# ai.net
KiCad netlist of a schematic drawn in Altium Designer
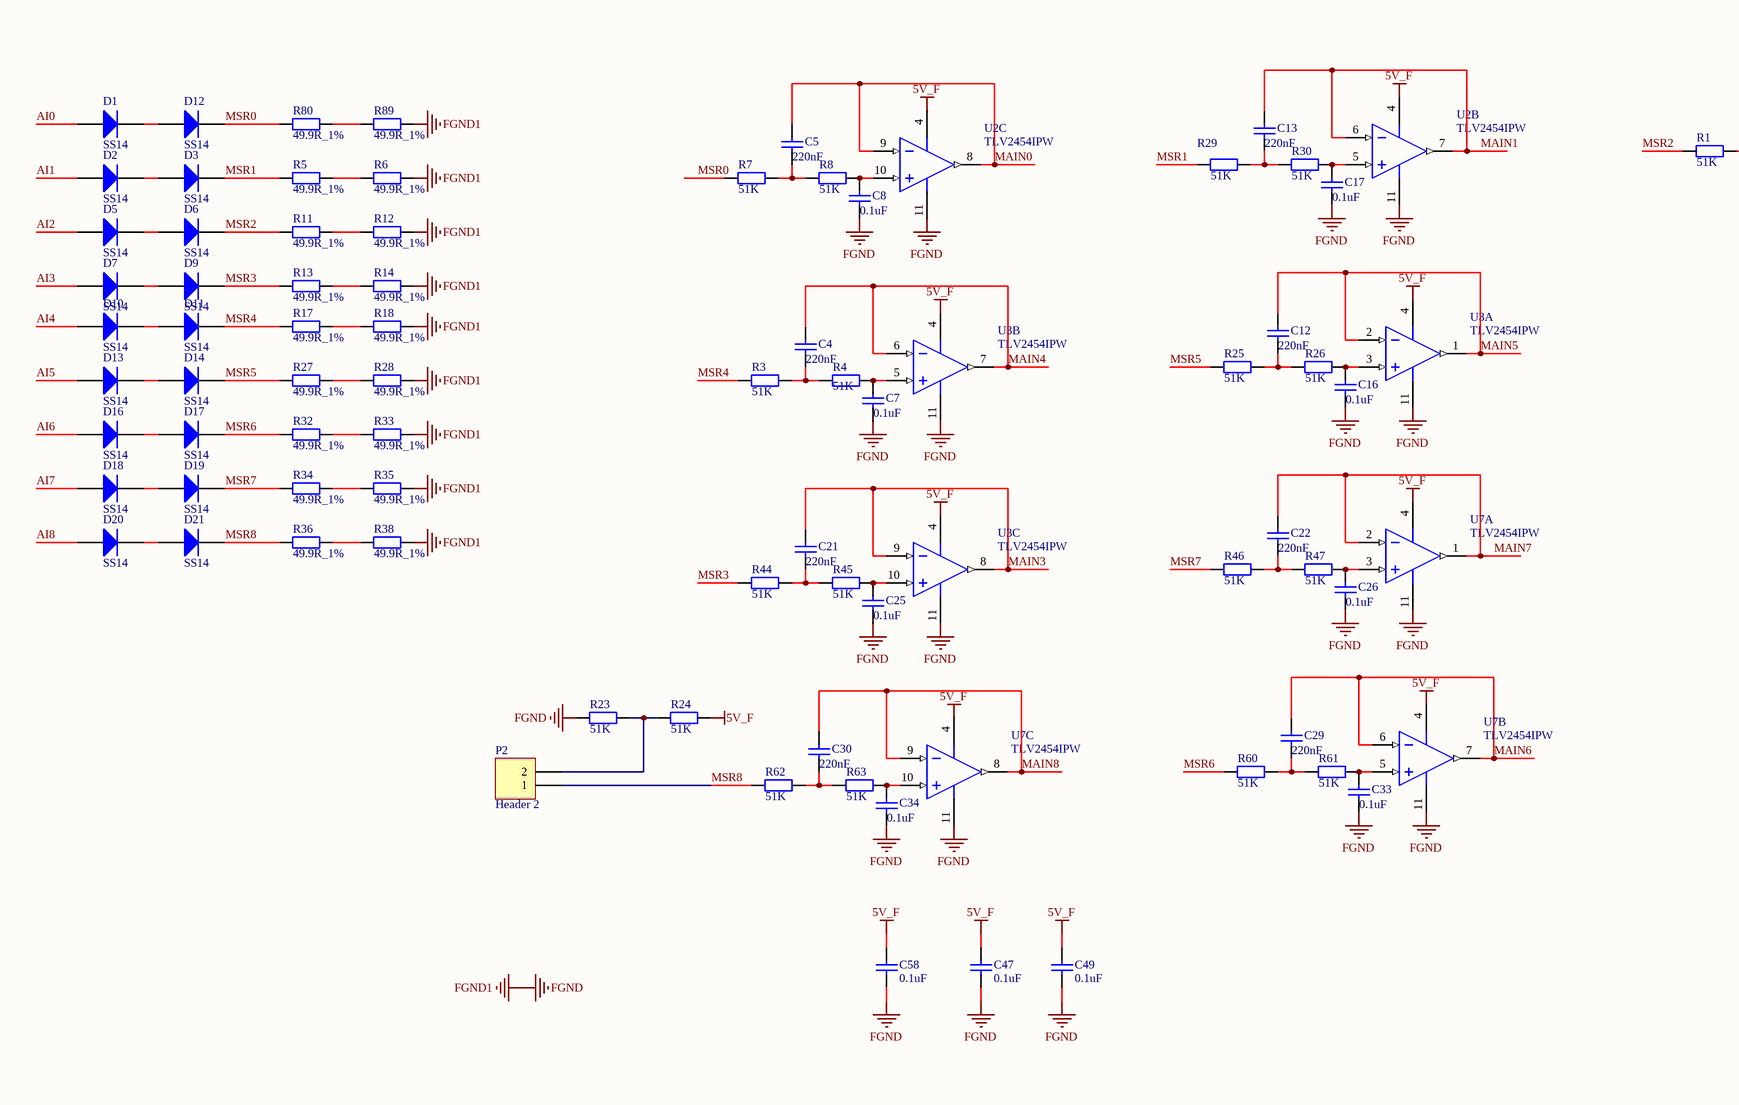
[diagram p0: ai.SchDoc, top left]
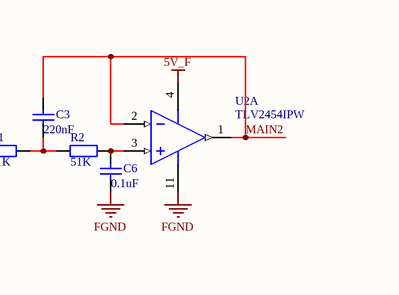
[diagram p1: ai.SchDoc, top right]
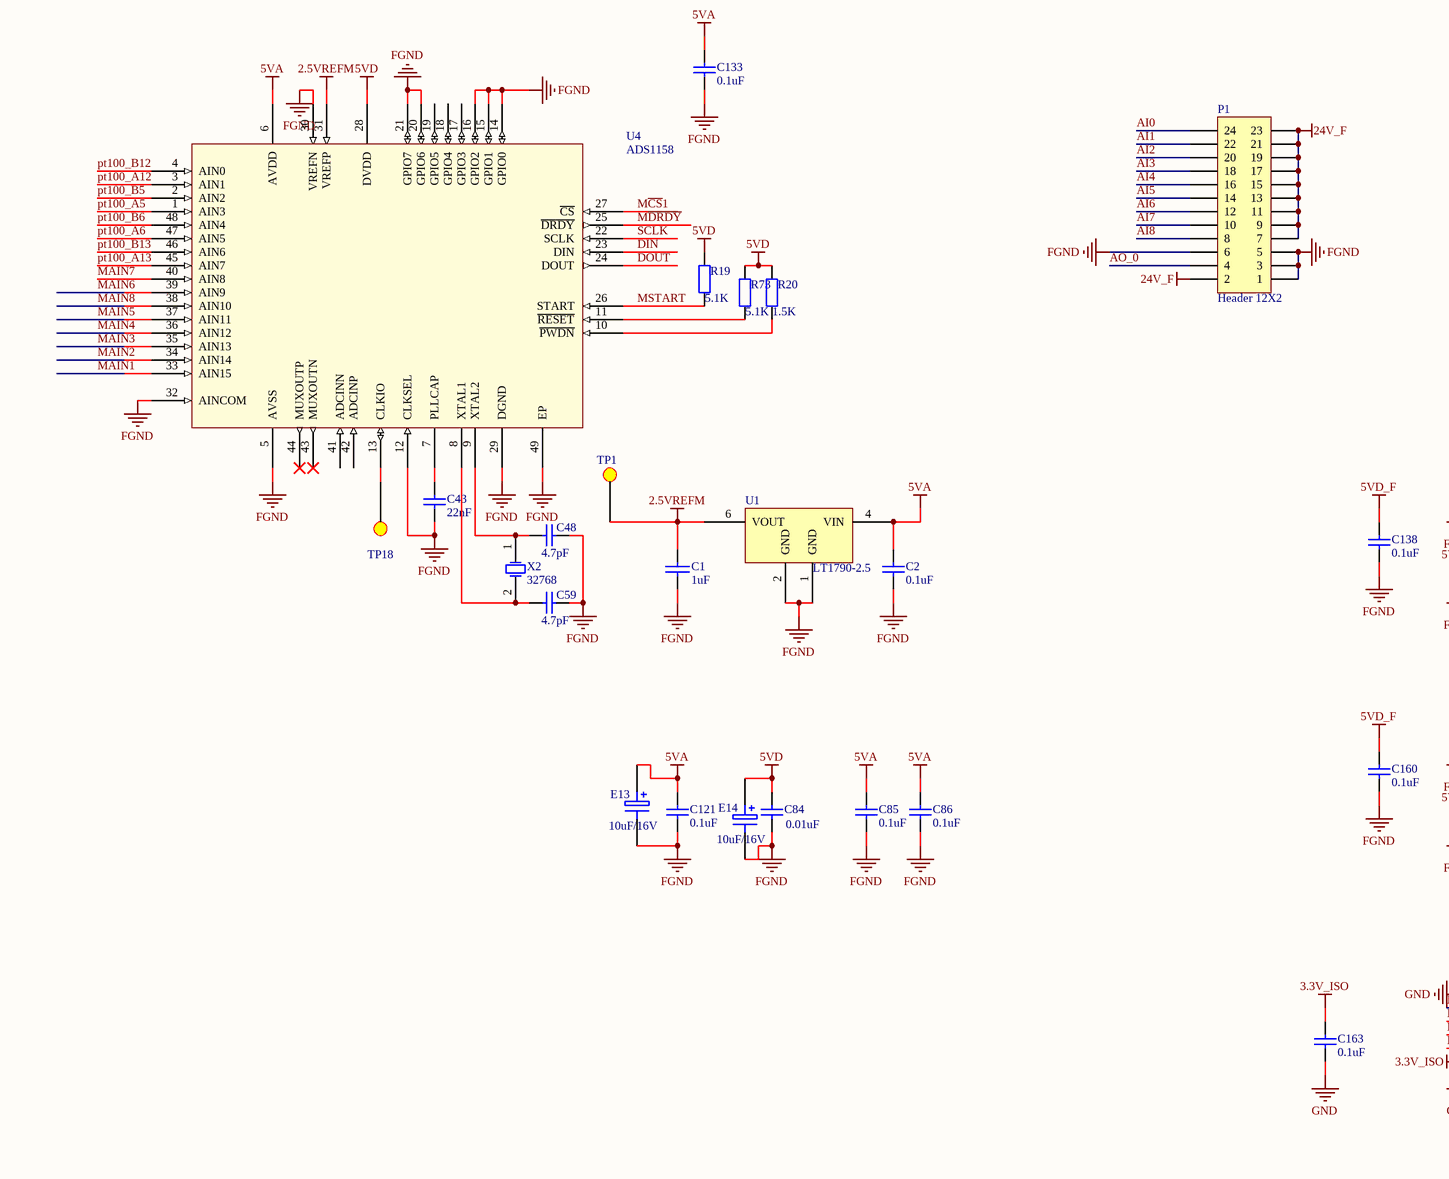
[diagram p2: ai.SchDoc, bottom left]
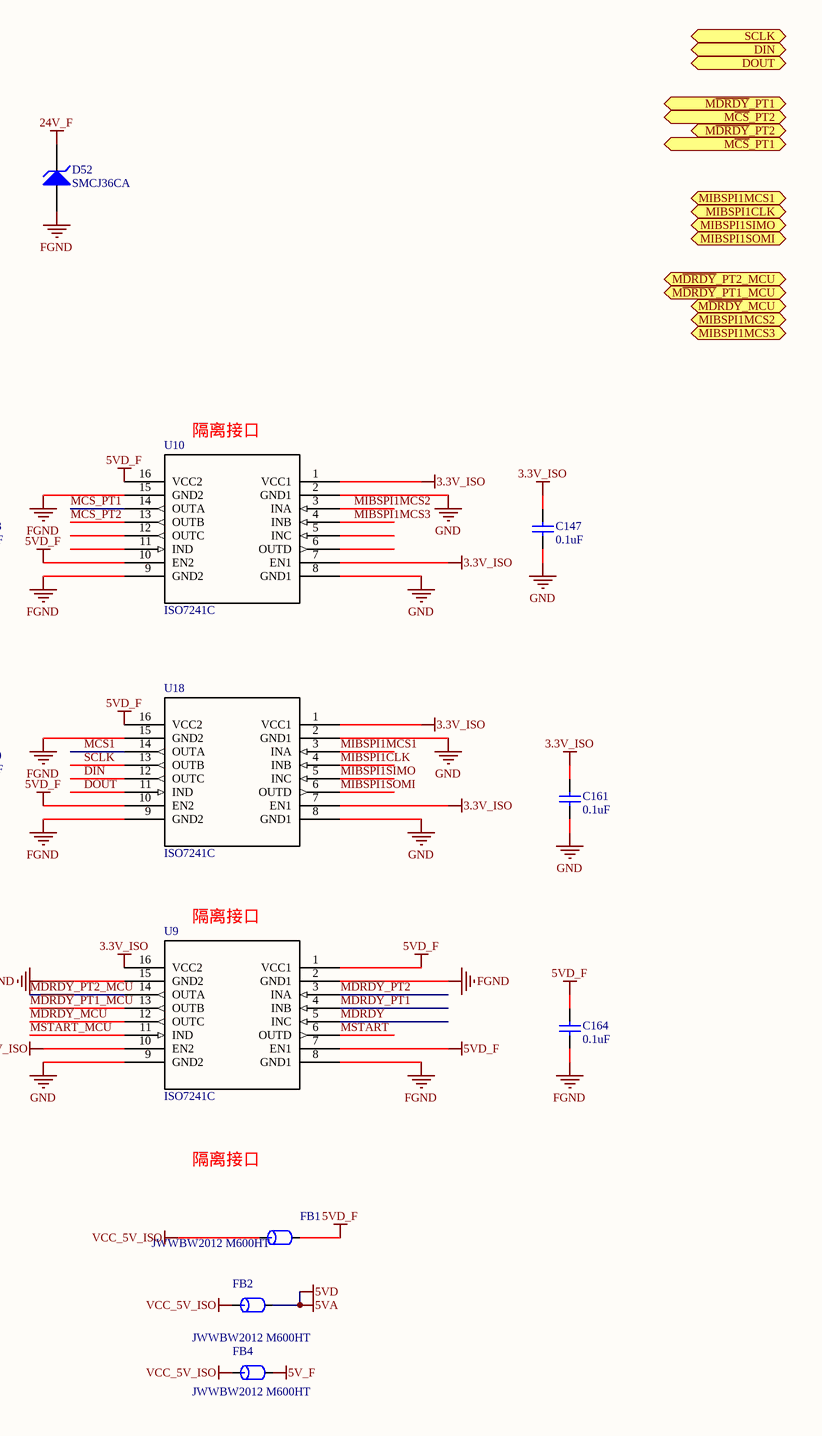
[diagram p3: ai.SchDoc, bottom right]

(export (version "E")
  (design (tool "Eeschema 10.0.6"))
  (components
    (comp (ref "C1")
      (value "1uF")
      (footprint "0603C")
      (description "Capacitor")
      (libsource (lib "*") (part "CAP"))
    )
    (comp (ref "C2")
      (value "0.1uF")
      (footprint "0603C")
      (description "Capacitor")
      (libsource (lib "Miscellaneous Devices") (part "Cap"))
    )
    (comp (ref "C3")
      (value "220nF")
      (footprint "0805C")
      (description "Capacitor")
      (libsource (lib "Miscellaneous Devices") (part "Cap"))
    )
    (comp (ref "C4")
      (value "220nF")
      (footprint "0805C")
      (description "Capacitor")
      (libsource (lib "Miscellaneous Devices") (part "Cap"))
    )
    (comp (ref "C5")
      (value "220nF")
      (footprint "0805C")
      (description "Capacitor")
      (libsource (lib "Miscellaneous Devices") (part "Cap"))
    )
    (comp (ref "C6")
      (value "0.1uF")
      (footprint "0603C")
      (description "Capacitor")
      (libsource (lib "Miscellaneous Devices") (part "Cap"))
    )
    (comp (ref "C7")
      (value "0.1uF")
      (footprint "0603C")
      (description "Capacitor")
      (libsource (lib "Miscellaneous Devices") (part "Cap"))
    )
    (comp (ref "C8")
      (value "0.1uF")
      (footprint "0603C")
      (description "Capacitor")
      (libsource (lib "Miscellaneous Devices") (part "Cap"))
    )
    (comp (ref "C12")
      (value "220nF")
      (footprint "0805C")
      (description "Capacitor")
      (libsource (lib "Miscellaneous Devices") (part "Cap"))
    )
    (comp (ref "C13")
      (value "220nF")
      (footprint "0805C")
      (description "Capacitor")
      (libsource (lib "Miscellaneous Devices") (part "Cap"))
    )
    (comp (ref "C16")
      (value "0.1uF")
      (footprint "0603C")
      (description "Capacitor")
      (libsource (lib "Miscellaneous Devices") (part "Cap"))
    )
    (comp (ref "C17")
      (value "0.1uF")
      (footprint "0603C")
      (description "Capacitor")
      (libsource (lib "Miscellaneous Devices") (part "Cap"))
    )
    (comp (ref "C21")
      (value "220nF")
      (footprint "0805C")
      (description "Capacitor")
      (libsource (lib "Miscellaneous Devices") (part "Cap"))
    )
    (comp (ref "C22")
      (value "220nF")
      (footprint "0805C")
      (description "Capacitor")
      (libsource (lib "Miscellaneous Devices") (part "Cap"))
    )
    (comp (ref "C25")
      (value "0.1uF")
      (footprint "0603C")
      (description "Capacitor")
      (libsource (lib "Miscellaneous Devices") (part "Cap"))
    )
    (comp (ref "C26")
      (value "0.1uF")
      (footprint "0603C")
      (description "Capacitor")
      (libsource (lib "Miscellaneous Devices") (part "Cap"))
    )
    (comp (ref "C29")
      (value "220nF")
      (footprint "0805C")
      (description "Capacitor")
      (libsource (lib "Miscellaneous Devices") (part "Cap"))
    )
    (comp (ref "C30")
      (value "220nF")
      (footprint "0805C")
      (description "Capacitor")
      (libsource (lib "Miscellaneous Devices") (part "Cap"))
    )
    (comp (ref "C33")
      (value "0.1uF")
      (footprint "0603C")
      (description "Capacitor")
      (libsource (lib "Miscellaneous Devices") (part "Cap"))
    )
    (comp (ref "C34")
      (value "0.1uF")
      (footprint "0603C")
      (description "Capacitor")
      (libsource (lib "Miscellaneous Devices") (part "Cap"))
    )
    (comp (ref "C43")
      (value "22nF")
      (footprint "0805C")
      (description "Capacitor")
      (libsource (lib "Miscellaneous Devices") (part "Cap"))
    )
    (comp (ref "C47")
      (value "0.1uF")
      (footprint "0603C")
      (description "Capacitor")
      (libsource (lib "Miscellaneous Devices") (part "Cap"))
    )
    (comp (ref "C48")
      (value "4.7pF")
      (footprint "0603C")
      (description "Capacitor")
      (libsource (lib "Miscellaneous Devices") (part "Cap"))
    )
    (comp (ref "C49")
      (value "0.1uF")
      (footprint "0603C")
      (description "Capacitor")
      (libsource (lib "Miscellaneous Devices") (part "Cap"))
    )
    (comp (ref "C58")
      (value "0.1uF")
      (footprint "0603C")
      (description "Capacitor")
      (libsource (lib "Miscellaneous Devices") (part "Cap"))
    )
    (comp (ref "C59")
      (value "4.7pF")
      (footprint "0603C")
      (description "Capacitor")
      (libsource (lib "Miscellaneous Devices") (part "Cap"))
    )
    (comp (ref "C84")
      (value "0.01uF")
      (footprint "0603C")
      (description "Capacitor")
      (libsource (lib "Miscellaneous Devices") (part "Cap"))
    )
    (comp (ref "C85")
      (value "0.1uF")
      (footprint "0603C")
      (description "Capacitor")
      (libsource (lib "Miscellaneous Devices") (part "Cap"))
    )
    (comp (ref "C86")
      (value "0.1uF")
      (footprint "0603C")
      (description "Capacitor")
      (libsource (lib "Miscellaneous Devices") (part "Cap"))
    )
    (comp (ref "C121")
      (value "0.1uF")
      (footprint "0603C")
      (description "Capacitor")
      (libsource (lib "Miscellaneous Devices") (part "Cap"))
    )
    (comp (ref "C133")
      (value "0.1uF")
      (footprint "0603C")
      (description "Capacitor")
      (libsource (lib "Miscellaneous Devices") (part "Cap"))
    )
    (comp (ref "C138")
      (value "0.1uF")
      (footprint "0603C")
      (description "Capacitor")
      (libsource (lib "Miscellaneous Devices") (part "Cap"))
    )
    (comp (ref "C147")
      (value "0.1uF")
      (footprint "0603C")
      (description "Capacitor")
      (libsource (lib "Miscellaneous Devices") (part "Cap"))
    )
    (comp (ref "C160")
      (value "0.1uF")
      (footprint "0603C")
      (description "Capacitor")
      (libsource (lib "Miscellaneous Devices") (part "Cap"))
    )
    (comp (ref "C161")
      (value "0.1uF")
      (footprint "0603C")
      (description "Capacitor")
      (libsource (lib "Miscellaneous Devices") (part "Cap"))
    )
    (comp (ref "C163")
      (value "0.1uF")
      (footprint "0603C")
      (description "Capacitor")
      (libsource (lib "Miscellaneous Devices") (part "Cap"))
    )
    (comp (ref "C164")
      (value "0.1uF")
      (footprint "0603C")
      (description "Capacitor")
      (libsource (lib "Miscellaneous Devices") (part "Cap"))
    )
    (comp (ref "D1")
      (value "SS14")
      (footprint "DO-214AC")
      (description "Default Diode")
      (libsource (lib "Miscellaneous Devices") (part "Diode"))
    )
    (comp (ref "D2")
      (value "SS14")
      (footprint "DO-214AC")
      (description "Default Diode")
      (libsource (lib "Miscellaneous Devices") (part "Diode"))
    )
    (comp (ref "D3")
      (value "SS14")
      (footprint "DO-214AC")
      (description "Default Diode")
      (libsource (lib "Miscellaneous Devices") (part "Diode"))
    )
    (comp (ref "D5")
      (value "SS14")
      (footprint "DO-214AC")
      (description "Default Diode")
      (libsource (lib "Miscellaneous Devices") (part "Diode"))
    )
    (comp (ref "D6")
      (value "SS14")
      (footprint "DO-214AC")
      (description "Default Diode")
      (libsource (lib "Miscellaneous Devices") (part "Diode"))
    )
    (comp (ref "D7")
      (value "SS14")
      (footprint "DO-214AC")
      (description "Default Diode")
      (libsource (lib "Miscellaneous Devices") (part "Diode"))
    )
    (comp (ref "D9")
      (value "SS14")
      (footprint "DO-214AC")
      (description "Default Diode")
      (libsource (lib "Miscellaneous Devices") (part "Diode"))
    )
    (comp (ref "D10")
      (value "SS14")
      (footprint "DO-214AC")
      (description "Default Diode")
      (libsource (lib "Miscellaneous Devices") (part "Diode"))
    )
    (comp (ref "D11")
      (value "SS14")
      (footprint "DO-214AC")
      (description "Default Diode")
      (libsource (lib "Miscellaneous Devices") (part "Diode"))
    )
    (comp (ref "D12")
      (value "SS14")
      (footprint "DO-214AC")
      (description "Default Diode")
      (libsource (lib "Miscellaneous Devices") (part "Diode"))
    )
    (comp (ref "D13")
      (value "SS14")
      (footprint "DO-214AC")
      (description "Default Diode")
      (libsource (lib "Miscellaneous Devices") (part "Diode"))
    )
    (comp (ref "D14")
      (value "SS14")
      (footprint "DO-214AC")
      (description "Default Diode")
      (libsource (lib "Miscellaneous Devices") (part "Diode"))
    )
    (comp (ref "D16")
      (value "SS14")
      (footprint "DO-214AC")
      (description "Default Diode")
      (libsource (lib "Miscellaneous Devices") (part "Diode"))
    )
    (comp (ref "D17")
      (value "SS14")
      (footprint "DO-214AC")
      (description "Default Diode")
      (libsource (lib "Miscellaneous Devices") (part "Diode"))
    )
    (comp (ref "D18")
      (value "SS14")
      (footprint "DO-214AC")
      (description "Default Diode")
      (libsource (lib "Miscellaneous Devices") (part "Diode"))
    )
    (comp (ref "D19")
      (value "SS14")
      (footprint "DO-214AC")
      (description "Default Diode")
      (libsource (lib "Miscellaneous Devices") (part "Diode"))
    )
    (comp (ref "D20")
      (value "SS14")
      (footprint "DO-214AC")
      (description "Default Diode")
      (libsource (lib "Miscellaneous Devices") (part "Diode"))
    )
    (comp (ref "D21")
      (value "SS14")
      (footprint "DO-214AC")
      (description "Default Diode")
      (libsource (lib "Miscellaneous Devices") (part "Diode"))
    )
    (comp (ref "D52")
      (value "SMCJ36CA")
      (footprint "SMC")
      (description "SMBJ36CA")
      (libsource (lib "Miscellaneous Devices") (part "D Zener"))
    )
    (comp (ref "E13")
      (value "10uF/16V")
      (footprint "C3528")
      (description "Electrolytic Capacitor")
      (libsource (lib "*") (part "ELECTRO1"))
    )
    (comp (ref "E14")
      (value "10uF/16V")
      (footprint "C3528")
      (description "Electrolytic Capacitor")
      (libsource (lib "*") (part "ELECTRO1"))
    )
    (comp (ref "FB1")
      (value "JWWBW2012 M600HT")
      (footprint "0805R")
      (libsource (lib "Schlib_20110825") (part "FB"))
    )
    (comp (ref "FB2")
      (value "JWWBW2012 M600HT")
      (footprint "0805R")
      (libsource (lib "Schlib_20110825") (part "FB"))
    )
    (comp (ref "FB4")
      (value "JWWBW2012 M600HT")
      (footprint "0805R")
      (libsource (lib "Schlib_20110825") (part "FB"))
    )
    (comp (ref "P1")
      (value "Header 12X2")
      (footprint "XH2.54_2x12")
      (description "Header, 12-Pin, Dual row")
      (libsource (lib "Miscellaneous Connectors") (part "Header 12X2"))
    )
    (comp (ref "P2")
      (value "Header 2")
      (footprint "HDR1X2")
      (description "Header, 2-Pin")
      (libsource (lib "Miscellaneous Connectors") (part "Header 2"))
    )
    (comp (ref "R1") (value "51K") (footprint "0603R") (libsource (lib "MQlibrary") (part "Res0805M")))
    (comp (ref "R2") (value "51K") (footprint "0603R") (libsource (lib "MQlibrary") (part "Res0805M")))
    (comp (ref "R3") (value "51K") (footprint "0603R") (libsource (lib "MQlibrary") (part "Res0805M")))
    (comp (ref "R4") (value "51K") (footprint "0603R") (libsource (lib "MQlibrary") (part "Res0805M")))
    (comp (ref "R5") (value "49.9R_1%") (footprint "0805R") (libsource (lib "MQlibrary") (part "Res0805M")))
    (comp (ref "R6") (value "49.9R_1%") (footprint "0805R") (libsource (lib "MQlibrary") (part "Res0805M")))
    (comp (ref "R7") (value "51K") (footprint "0603R") (libsource (lib "MQlibrary") (part "Res0805M")))
    (comp (ref "R8") (value "51K") (footprint "0603R") (libsource (lib "MQlibrary") (part "Res0805M")))
    (comp (ref "R11") (value "49.9R_1%") (footprint "0805R") (libsource (lib "MQlibrary") (part "Res0805M")))
    (comp (ref "R12") (value "49.9R_1%") (footprint "0805R") (libsource (lib "MQlibrary") (part "Res0805M")))
    (comp (ref "R13") (value "49.9R_1%") (footprint "0805R") (libsource (lib "MQlibrary") (part "Res0805M")))
    (comp (ref "R14") (value "49.9R_1%") (footprint "0805R") (libsource (lib "MQlibrary") (part "Res0805M")))
    (comp (ref "R17") (value "49.9R_1%") (footprint "0805R") (libsource (lib "MQlibrary") (part "Res0805M")))
    (comp (ref "R18") (value "49.9R_1%") (footprint "0805R") (libsource (lib "MQlibrary") (part "Res0805M")))
    (comp (ref "R19") (value "5.1K") (footprint "0603R") (libsource (lib "") (part "Res0805M_2")))
    (comp (ref "R20") (value "1.5K") (footprint "0603R") (libsource (lib "") (part "Res0805M_2")))
    (comp (ref "R23") (value "51K") (footprint "0603R") (libsource (lib "") (part "Res0805M_1")))
    (comp (ref "R24") (value "51K") (footprint "0603R") (libsource (lib "") (part "Res0805M_1")))
    (comp (ref "R25") (value "51K") (footprint "0603R") (libsource (lib "MQlibrary") (part "Res0805M")))
    (comp (ref "R26") (value "51K") (footprint "0603R") (libsource (lib "MQlibrary") (part "Res0805M")))
    (comp (ref "R27") (value "49.9R_1%") (footprint "0805R") (libsource (lib "MQlibrary") (part "Res0805M")))
    (comp (ref "R28") (value "49.9R_1%") (footprint "0805R") (libsource (lib "MQlibrary") (part "Res0805M")))
    (comp (ref "R29") (value "51K") (footprint "0603R") (libsource (lib "MQlibrary") (part "Res0805M")))
    (comp (ref "R30") (value "51K") (footprint "0603R") (libsource (lib "MQlibrary") (part "Res0805M")))
    (comp (ref "R32") (value "49.9R_1%") (footprint "0805R") (libsource (lib "MQlibrary") (part "Res0805M")))
    (comp (ref "R33") (value "49.9R_1%") (footprint "0805R") (libsource (lib "MQlibrary") (part "Res0805M")))
    (comp (ref "R34") (value "49.9R_1%") (footprint "0805R") (libsource (lib "MQlibrary") (part "Res0805M")))
    (comp (ref "R35") (value "49.9R_1%") (footprint "0805R") (libsource (lib "MQlibrary") (part "Res0805M")))
    (comp (ref "R36") (value "49.9R_1%") (footprint "0805R") (libsource (lib "MQlibrary") (part "Res0805M")))
    (comp (ref "R38") (value "49.9R_1%") (footprint "0805R") (libsource (lib "MQlibrary") (part "Res0805M")))
    (comp (ref "R44") (value "51K") (footprint "0603R") (libsource (lib "MQlibrary") (part "Res0805M")))
    (comp (ref "R45") (value "51K") (footprint "0603R") (libsource (lib "MQlibrary") (part "Res0805M")))
    (comp (ref "R46") (value "51K") (footprint "0603R") (libsource (lib "MQlibrary") (part "Res0805M")))
    (comp (ref "R47") (value "51K") (footprint "0603R") (libsource (lib "MQlibrary") (part "Res0805M")))
    (comp (ref "R60") (value "51K") (footprint "0603R") (libsource (lib "MQlibrary") (part "Res0805M")))
    (comp (ref "R61") (value "51K") (footprint "0603R") (libsource (lib "MQlibrary") (part "Res0805M")))
    (comp (ref "R62") (value "51K") (footprint "0603R") (libsource (lib "MQlibrary") (part "Res0805M")))
    (comp (ref "R63") (value "51K") (footprint "0603R") (libsource (lib "MQlibrary") (part "Res0805M")))
    (comp (ref "R73") (value "5.1K") (footprint "0603R") (libsource (lib "") (part "Res0805M_2")))
    (comp (ref "R80") (value "49.9R_1%") (footprint "0805R") (libsource (lib "MQlibrary") (part "Res0805M")))
    (comp (ref "R89") (value "49.9R_1%") (footprint "0805R") (libsource (lib "MQlibrary") (part "Res0805M")))
    (comp (ref "TP1")
      (value "TEST_POINT")
      (footprint "TPD")
      (libsource (lib "基带芯片OEM板_V1P0_张猛_20120921") (part "TEST_POINT"))
    )
    (comp (ref "TP18")
      (value "TEST_POINT")
      (footprint "TPD")
      (libsource (lib "基带芯片OEM板_V1P0_张猛_20120921") (part "TEST_POINT"))
    )
    (comp (ref "U1")
      (value "LT1790-2.5")
      (footprint "SOT23-6")
      (description "2.5V Micropower SOT-23  Low Dropout Reference")
      (libsource (lib "Schlib") (part "LT1790-2.5"))
    )
    (comp (ref "U2")
      (value "TLV2454IPW")
      (footprint "TSSOP14")
      (description "Quad High-speed, Ultra Low-power, Single-Supply TTL comparator")
      (libsource (lib "Maxim Analog Comparator") (part "MAX908EPD"))
    )
    (comp (ref "U3")
      (value "TLV2454IPW")
      (footprint "TSSOP14")
      (description "Quad High-speed, Ultra Low-power, Single-Supply TTL comparator")
      (libsource (lib "Maxim Analog Comparator") (part "MAX908EPD"))
    )
    (comp (ref "U4")
      (value "ADS1158")
      (footprint "S-PVFQN-N48")
      (description "16-Channel, 16-Bit Analog-to-Digital Converter")
      (libsource (lib "Schlib") (part "ADS1158"))
    )
    (comp (ref "U7")
      (value "TLV2454IPW")
      (footprint "TSSOP14")
      (description "Quad High-speed, Ultra Low-power, Single-Supply TTL comparator")
      (libsource (lib "Maxim Analog Comparator") (part "MAX908EPD"))
    )
    (comp (ref "U9") (value "ISO7241C") (footprint "SOIC16") (libsource (lib "DI16") (part "ISO7241C")))
    (comp (ref "U10") (value "ISO7241C") (footprint "SOIC16") (libsource (lib "DI16") (part "ISO7241C")))
    (comp (ref "U18") (value "ISO7241C") (footprint "SOIC16") (libsource (lib "DI16") (part "ISO7241C")))
    (comp (ref "X2")
      (value "32768")
      (footprint "A")
      (description "Crystal Oscillator")
      (libsource (lib "Miscellaneous Devices") (part "XTAL"))
    )
  )
  (nets
    (net (code "1") (name "/AI0") (class "Default")
      (node (ref "D1") (pin "1") (pinfunction "A_1") (pintype "passive"))
      (node (ref "P1") (pin "24") (pinfunction "24_24") (pintype "passive"))
    )
    (net (code "2") (name "/AI1") (class "Default")
      (node (ref "D2") (pin "1") (pinfunction "A_1") (pintype "passive"))
      (node (ref "P1") (pin "22") (pinfunction "22_22") (pintype "passive"))
    )
    (net (code "3") (name "/AI2") (class "Default")
      (node (ref "D5") (pin "1") (pinfunction "A_1") (pintype "passive"))
      (node (ref "P1") (pin "20") (pinfunction "20_20") (pintype "passive"))
    )
    (net (code "4") (name "/AI3") (class "Default")
      (node (ref "D7") (pin "1") (pinfunction "A_1") (pintype "passive"))
      (node (ref "P1") (pin "18") (pinfunction "18_18") (pintype "passive"))
    )
    (net (code "5") (name "/AI4") (class "Default")
      (node (ref "D10") (pin "1") (pinfunction "A_1") (pintype "passive"))
      (node (ref "P1") (pin "16") (pinfunction "16_16") (pintype "passive"))
    )
    (net (code "6") (name "/AI5") (class "Default")
      (node (ref "D13") (pin "1") (pinfunction "A_1") (pintype "passive"))
      (node (ref "P1") (pin "14") (pinfunction "14_14") (pintype "passive"))
    )
    (net (code "7") (name "/AI6") (class "Default")
      (node (ref "D16") (pin "1") (pinfunction "A_1") (pintype "passive"))
      (node (ref "P1") (pin "12") (pinfunction "12_12") (pintype "passive"))
    )
    (net (code "8") (name "/AI7") (class "Default")
      (node (ref "D18") (pin "1") (pinfunction "A_1") (pintype "passive"))
      (node (ref "P1") (pin "10") (pinfunction "10_10") (pintype "passive"))
    )
    (net (code "9") (name "/AI8") (class "Default")
      (node (ref "D20") (pin "1") (pinfunction "A_1") (pintype "passive"))
      (node (ref "P1") (pin "8") (pinfunction "8_8") (pintype "passive"))
    )
    (net (code "10") (name "/AO_0") (class "Default")
      (node (ref "P1") (pin "4") (pinfunction "4_4") (pintype "passive"))
    )
    (net (code "11") (name "/DIN") (class "Default")
      (node (ref "U18") (pin "12") (pinfunction "OUTC_12") (pintype "output"))
      (node (ref "U4") (pin "23") (pinfunction "DIN_23") (pintype "input"))
    )
    (net (code "12") (name "/DOUT") (class "Default")
      (node (ref "U18") (pin "11") (pinfunction "IND_11") (pintype "input"))
      (node (ref "U4") (pin "24") (pinfunction "DOUT_24") (pintype "output"))
    )
    (net (code "13") (name "/MAIN0") (class "Default")
      (node (ref "C5") (pin "2") (pinfunction "2_2") (pintype "passive"))
      (node (ref "U2") (pin "8") (pinfunction "OUT_8") (pintype "output"))
      (node (ref "U2") (pin "9") (pinfunction "IN-_9") (pintype "input"))
    )
    (net (code "14") (name "/MAIN1") (class "Default")
      (node (ref "C13") (pin "2") (pinfunction "2_2") (pintype "passive"))
      (node (ref "U2") (pin "6") (pinfunction "IN-_6") (pintype "input"))
      (node (ref "U2") (pin "7") (pinfunction "OUT_7") (pintype "output"))
      (node (ref "U4") (pin "33") (pinfunction "AIN15_33") (pintype "input"))
    )
    (net (code "15") (name "/MAIN2") (class "Default")
      (node (ref "C3") (pin "2") (pinfunction "2_2") (pintype "passive"))
      (node (ref "U2") (pin "1") (pinfunction "OUT_1") (pintype "output"))
      (node (ref "U2") (pin "2") (pinfunction "IN-_2") (pintype "input"))
      (node (ref "U4") (pin "34") (pinfunction "AIN14_34") (pintype "input"))
    )
    (net (code "16") (name "/MAIN3") (class "Default")
      (node (ref "C21") (pin "2") (pinfunction "2_2") (pintype "passive"))
      (node (ref "U3") (pin "8") (pinfunction "OUT_8") (pintype "output"))
      (node (ref "U3") (pin "9") (pinfunction "IN-_9") (pintype "input"))
      (node (ref "U4") (pin "35") (pinfunction "AIN13_35") (pintype "input"))
    )
    (net (code "17") (name "/MAIN4") (class "Default")
      (node (ref "C4") (pin "2") (pinfunction "2_2") (pintype "passive"))
      (node (ref "U3") (pin "6") (pinfunction "IN-_6") (pintype "input"))
      (node (ref "U3") (pin "7") (pinfunction "OUT_7") (pintype "output"))
      (node (ref "U4") (pin "36") (pinfunction "AIN12_36") (pintype "input"))
    )
    (net (code "18") (name "/MAIN5") (class "Default")
      (node (ref "C12") (pin "2") (pinfunction "2_2") (pintype "passive"))
      (node (ref "U3") (pin "1") (pinfunction "OUT_1") (pintype "output"))
      (node (ref "U3") (pin "2") (pinfunction "IN-_2") (pintype "input"))
      (node (ref "U4") (pin "37") (pinfunction "AIN11_37") (pintype "input"))
    )
    (net (code "19") (name "/MAIN6") (class "Default")
      (node (ref "C29") (pin "2") (pinfunction "2_2") (pintype "passive"))
      (node (ref "U4") (pin "39") (pinfunction "AIN9_39") (pintype "input"))
      (node (ref "U7") (pin "6") (pinfunction "IN-_6") (pintype "input"))
      (node (ref "U7") (pin "7") (pinfunction "OUT_7") (pintype "output"))
    )
    (net (code "20") (name "/MAIN7") (class "Default")
      (node (ref "C22") (pin "2") (pinfunction "2_2") (pintype "passive"))
      (node (ref "U4") (pin "40") (pinfunction "AIN8_40") (pintype "input"))
      (node (ref "U7") (pin "1") (pinfunction "OUT_1") (pintype "output"))
      (node (ref "U7") (pin "2") (pinfunction "IN-_2") (pintype "input"))
    )
    (net (code "21") (name "/MAIN8") (class "Default")
      (node (ref "C30") (pin "2") (pinfunction "2_2") (pintype "passive"))
      (node (ref "U4") (pin "38") (pinfunction "AIN10_38") (pintype "input"))
      (node (ref "U7") (pin "8") (pinfunction "OUT_8") (pintype "output"))
      (node (ref "U7") (pin "9") (pinfunction "IN-_9") (pintype "input"))
    )
    (net (code "22") (name "/MIBSPI1CLK") (class "Default")
      (node (ref "U18") (pin "4") (pinfunction "INB_4") (pintype "input"))
    )
    (net (code "23") (name "/MIBSPI1MCS1") (class "Default")
      (node (ref "U18") (pin "3") (pinfunction "INA_3") (pintype "input"))
    )
    (net (code "24") (name "/MIBSPI1MCS2") (class "Default")
      (node (ref "U10") (pin "3") (pinfunction "INA_3") (pintype "input"))
    )
    (net (code "25") (name "/MIBSPI1MCS3") (class "Default")
      (node (ref "U10") (pin "4") (pinfunction "INB_4") (pintype "input"))
    )
    (net (code "26") (name "/MIBSPI1SIMO") (class "Default")
      (node (ref "U18") (pin "5") (pinfunction "INC_5") (pintype "input"))
    )
    (net (code "27") (name "/MIBSPI1SOMI") (class "Default")
      (node (ref "U18") (pin "6") (pinfunction "OUTD_6") (pintype "output"))
    )
    (net (code "28") (name "/MSR0") (class "Default")
      (node (ref "D12") (pin "2") (pinfunction "K_2") (pintype "passive"))
      (node (ref "R7") (pin "2") (pinfunction "2_2") (pintype "passive"))
      (node (ref "R80") (pin "2") (pinfunction "2_2") (pintype "passive"))
    )
    (net (code "29") (name "/MSR1") (class "Default")
      (node (ref "D3") (pin "2") (pinfunction "K_2") (pintype "passive"))
      (node (ref "R29") (pin "2") (pinfunction "2_2") (pintype "passive"))
      (node (ref "R5") (pin "2") (pinfunction "2_2") (pintype "passive"))
    )
    (net (code "30") (name "/MSR2") (class "Default")
      (node (ref "D6") (pin "2") (pinfunction "K_2") (pintype "passive"))
      (node (ref "R1") (pin "2") (pinfunction "2_2") (pintype "passive"))
      (node (ref "R11") (pin "2") (pinfunction "2_2") (pintype "passive"))
    )
    (net (code "31") (name "/MSR3") (class "Default")
      (node (ref "D9") (pin "2") (pinfunction "K_2") (pintype "passive"))
      (node (ref "R13") (pin "2") (pinfunction "2_2") (pintype "passive"))
      (node (ref "R44") (pin "2") (pinfunction "2_2") (pintype "passive"))
    )
    (net (code "32") (name "/MSR4") (class "Default")
      (node (ref "D11") (pin "2") (pinfunction "K_2") (pintype "passive"))
      (node (ref "R17") (pin "2") (pinfunction "2_2") (pintype "passive"))
      (node (ref "R3") (pin "2") (pinfunction "2_2") (pintype "passive"))
    )
    (net (code "33") (name "/MSR5") (class "Default")
      (node (ref "D14") (pin "2") (pinfunction "K_2") (pintype "passive"))
      (node (ref "R25") (pin "2") (pinfunction "2_2") (pintype "passive"))
      (node (ref "R27") (pin "2") (pinfunction "2_2") (pintype "passive"))
    )
    (net (code "34") (name "/MSR6") (class "Default")
      (node (ref "D17") (pin "2") (pinfunction "K_2") (pintype "passive"))
      (node (ref "R32") (pin "2") (pinfunction "2_2") (pintype "passive"))
      (node (ref "R60") (pin "2") (pinfunction "2_2") (pintype "passive"))
    )
    (net (code "35") (name "/MSR7") (class "Default")
      (node (ref "D19") (pin "2") (pinfunction "K_2") (pintype "passive"))
      (node (ref "R34") (pin "2") (pinfunction "2_2") (pintype "passive"))
      (node (ref "R46") (pin "2") (pinfunction "2_2") (pintype "passive"))
    )
    (net (code "36") (name "/MSR8") (class "Default")
      (node (ref "D21") (pin "2") (pinfunction "K_2") (pintype "passive"))
      (node (ref "P2") (pin "1") (pinfunction "1_1") (pintype "passive"))
      (node (ref "R36") (pin "2") (pinfunction "2_2") (pintype "passive"))
      (node (ref "R62") (pin "2") (pinfunction "2_2") (pintype "passive"))
    )
    (net (code "37") (name "/MSTART") (class "Default")
      (node (ref "R19") (pin "2") (pinfunction "2_2") (pintype "passive"))
      (node (ref "U4") (pin "26") (pinfunction "START_26") (pintype "input"))
      (node (ref "U9") (pin "6") (pinfunction "OUTD_6") (pintype "output"))
    )
    (net (code "38") (name "/MSTART_MCU") (class "Default")
      (node (ref "U9") (pin "11") (pinfunction "IND_11") (pintype "input"))
    )
    (net (code "39") (name "/M~{CS}1") (class "Default")
      (node (ref "U18") (pin "14") (pinfunction "OUTA_14") (pintype "output"))
      (node (ref "U4") (pin "27") (pinfunction "~{CS}_27") (pintype "input"))
    )
    (net (code "40") (name "/M~{CS}_PT1") (class "Default")
      (node (ref "U10") (pin "14") (pinfunction "OUTA_14") (pintype "output"))
    )
    (net (code "41") (name "/M~{CS}_PT2") (class "Default")
      (node (ref "U10") (pin "13") (pinfunction "OUTB_13") (pintype "output"))
    )
    (net (code "42") (name "/M~{DRDY}") (class "Default")
      (node (ref "U4") (pin "25") (pinfunction "~{DRDY}_25") (pintype "output"))
      (node (ref "U9") (pin "5") (pinfunction "INC_5") (pintype "input"))
    )
    (net (code "43") (name "/M~{DRDY}_MCU") (class "Default")
      (node (ref "U9") (pin "12") (pinfunction "OUTC_12") (pintype "output"))
    )
    (net (code "44") (name "/M~{DRDY}_PT1") (class "Default")
      (node (ref "U9") (pin "4") (pinfunction "INB_4") (pintype "input"))
    )
    (net (code "45") (name "/M~{DRDY}_PT1_MCU") (class "Default")
      (node (ref "U9") (pin "13") (pinfunction "OUTB_13") (pintype "output"))
    )
    (net (code "46") (name "/M~{DRDY}_PT2") (class "Default")
      (node (ref "U9") (pin "3") (pinfunction "INA_3") (pintype "input"))
    )
    (net (code "47") (name "/M~{DRDY}_PT2_MCU") (class "Default")
      (node (ref "U9") (pin "14") (pinfunction "OUTA_14") (pintype "output"))
    )
    (net (code "48") (name "/SCLK") (class "Default")
      (node (ref "U18") (pin "13") (pinfunction "OUTB_13") (pintype "output"))
      (node (ref "U4") (pin "22") (pinfunction "SCLK_22") (pintype "input"))
    )
    (net (code "49") (name "/pt100_A5") (class "Default")
      (node (ref "U4") (pin "1") (pinfunction "AIN3_1") (pintype "input"))
    )
    (net (code "50") (name "/pt100_A6") (class "Default")
      (node (ref "U4") (pin "47") (pinfunction "AIN5_47") (pintype "input"))
    )
    (net (code "51") (name "/pt100_A12") (class "Default")
      (node (ref "U4") (pin "3") (pinfunction "AIN1_3") (pintype "input"))
    )
    (net (code "52") (name "/pt100_A13") (class "Default")
      (node (ref "U4") (pin "45") (pinfunction "AIN7_45") (pintype "input"))
    )
    (net (code "53") (name "/pt100_B5") (class "Default")
      (node (ref "U4") (pin "2") (pinfunction "AIN2_2") (pintype "input"))
    )
    (net (code "54") (name "/pt100_B6") (class "Default")
      (node (ref "U4") (pin "48") (pinfunction "AIN4_48") (pintype "input"))
    )
    (net (code "55") (name "/pt100_B12") (class "Default")
      (node (ref "U4") (pin "4") (pinfunction "AIN0_4") (pintype "input"))
    )
    (net (code "56") (name "/pt100_B13") (class "Default")
      (node (ref "U4") (pin "46") (pinfunction "AIN6_46") (pintype "input"))
    )
    (net (code "57") (name "2.5VREFM") (class "Default")
      (node (ref "C1") (pin "1") (pinfunction "1_1") (pintype "passive"))
      (node (ref "TP1") (pin "1") (pinfunction "1_1") (pintype "passive"))
      (node (ref "U1") (pin "6") (pinfunction "VOUT_6") (pintype "power_in"))
      (node (ref "U4") (pin "31") (pinfunction "VREFP_31") (pintype "input"))
    )
    (net (code "58") (name "3.3V_ISO") (class "Default")
      (node (ref "C147") (pin "2") (pinfunction "2_2") (pintype "passive"))
      (node (ref "C161") (pin "2") (pinfunction "2_2") (pintype "passive"))
      (node (ref "C163") (pin "2") (pinfunction "2_2") (pintype "passive"))
      (node (ref "U10") (pin "1") (pinfunction "VCC1_1") (pintype "power_in"))
      (node (ref "U10") (pin "7") (pinfunction "EN1_7") (pintype "passive"))
      (node (ref "U18") (pin "1") (pinfunction "VCC1_1") (pintype "power_in"))
      (node (ref "U18") (pin "7") (pinfunction "EN1_7") (pintype "passive"))
      (node (ref "U9") (pin "10") (pinfunction "EN2_10") (pintype "passive"))
      (node (ref "U9") (pin "16") (pinfunction "VCC2_16") (pintype "power_in"))
    )
    (net (code "59") (name "5VA") (class "Default")
      (node (ref "C121") (pin "2") (pinfunction "2_2") (pintype "passive"))
      (node (ref "C133") (pin "2") (pinfunction "2_2") (pintype "passive"))
      (node (ref "C2") (pin "2") (pinfunction "2_2") (pintype "passive"))
      (node (ref "C84") (pin "2") (pinfunction "2_2") (pintype "passive"))
      (node (ref "C85") (pin "2") (pinfunction "2_2") (pintype "passive"))
      (node (ref "C86") (pin "2") (pinfunction "2_2") (pintype "passive"))
      (node (ref "E13") (pin "1") (pinfunction "1_1") (pintype "passive"))
      (node (ref "E14") (pin "1") (pinfunction "1_1") (pintype "passive"))
      (node (ref "FB2") (pin "2") (pintype "passive"))
      (node (ref "R19") (pin "1") (pinfunction "1_1") (pintype "passive"))
      (node (ref "R20") (pin "1") (pinfunction "1_1") (pintype "passive"))
      (node (ref "R73") (pin "1") (pinfunction "1_1") (pintype "passive"))
      (node (ref "U1") (pin "4") (pinfunction "VIN_4") (pintype "power_in"))
      (node (ref "U4") (pin "28") (pinfunction "DVDD_28") (pintype "power_in"))
      (node (ref "U4") (pin "6") (pinfunction "AVDD_6") (pintype "passive"))
    )
    (net (code "60") (name "5VD_F") (class "Default")
      (node (ref "C138") (pin "2") (pinfunction "2_2") (pintype "passive"))
      (node (ref "C160") (pin "2") (pinfunction "2_2") (pintype "passive"))
      (node (ref "C164") (pin "2") (pinfunction "2_2") (pintype "passive"))
      (node (ref "FB1") (pin "2") (pintype "passive"))
      (node (ref "U10") (pin "10") (pinfunction "EN2_10") (pintype "passive"))
      (node (ref "U10") (pin "16") (pinfunction "VCC2_16") (pintype "power_in"))
      (node (ref "U18") (pin "10") (pinfunction "EN2_10") (pintype "passive"))
      (node (ref "U18") (pin "16") (pinfunction "VCC2_16") (pintype "power_in"))
      (node (ref "U9") (pin "1") (pinfunction "VCC1_1") (pintype "power_in"))
      (node (ref "U9") (pin "7") (pinfunction "EN1_7") (pintype "passive"))
    )
    (net (code "61") (name "5V_F") (class "Default")
      (node (ref "C47") (pin "2") (pinfunction "2_2") (pintype "passive"))
      (node (ref "C49") (pin "2") (pinfunction "2_2") (pintype "passive"))
      (node (ref "C58") (pin "2") (pinfunction "2_2") (pintype "passive"))
      (node (ref "FB4") (pin "2") (pintype "passive"))
      (node (ref "R24") (pin "2") (pinfunction "2_2") (pintype "passive"))
      (node (ref "U2") (pin "4") (pinfunction "V+_4") (pintype "power_in"))
      (node (ref "U3") (pin "4") (pinfunction "V+_4") (pintype "power_in"))
      (node (ref "U7") (pin "4") (pinfunction "V+_4") (pintype "power_in"))
    )
    (net (code "62") (name "24V_F") (class "Default")
      (node (ref "D52") (pin "2") (pinfunction "K_2") (pintype "passive"))
      (node (ref "P1") (pin "11") (pinfunction "11_11") (pintype "passive"))
      (node (ref "P1") (pin "13") (pinfunction "13_13") (pintype "passive"))
      (node (ref "P1") (pin "15") (pinfunction "15_15") (pintype "passive"))
      (node (ref "P1") (pin "17") (pinfunction "17_17") (pintype "passive"))
      (node (ref "P1") (pin "19") (pinfunction "19_19") (pintype "passive"))
      (node (ref "P1") (pin "2") (pinfunction "2_2") (pintype "passive"))
      (node (ref "P1") (pin "21") (pinfunction "21_21") (pintype "passive"))
      (node (ref "P1") (pin "23") (pinfunction "23_23") (pintype "passive"))
      (node (ref "P1") (pin "7") (pinfunction "7_7") (pintype "passive"))
      (node (ref "P1") (pin "9") (pinfunction "9_9") (pintype "passive"))
    )
    (net (code "63") (name "FGND") (class "Default")
      (node (ref "C1") (pin "2") (pinfunction "2_2") (pintype "passive"))
      (node (ref "C121") (pin "1") (pinfunction "1_1") (pintype "passive"))
      (node (ref "C133") (pin "1") (pinfunction "1_1") (pintype "passive"))
      (node (ref "C138") (pin "1") (pinfunction "1_1") (pintype "passive"))
      (node (ref "C16") (pin "1") (pinfunction "1_1") (pintype "passive"))
      (node (ref "C160") (pin "1") (pinfunction "1_1") (pintype "passive"))
      (node (ref "C164") (pin "1") (pinfunction "1_1") (pintype "passive"))
      (node (ref "C17") (pin "1") (pinfunction "1_1") (pintype "passive"))
      (node (ref "C2") (pin "1") (pinfunction "1_1") (pintype "passive"))
      (node (ref "C25") (pin "1") (pinfunction "1_1") (pintype "passive"))
      (node (ref "C26") (pin "1") (pinfunction "1_1") (pintype "passive"))
      (node (ref "C33") (pin "1") (pinfunction "1_1") (pintype "passive"))
      (node (ref "C34") (pin "1") (pinfunction "1_1") (pintype "passive"))
      (node (ref "C43") (pin "2") (pinfunction "2_2") (pintype "passive"))
      (node (ref "C47") (pin "1") (pinfunction "1_1") (pintype "passive"))
      (node (ref "C48") (pin "2") (pinfunction "2_2") (pintype "passive"))
      (node (ref "C49") (pin "1") (pinfunction "1_1") (pintype "passive"))
      (node (ref "C58") (pin "1") (pinfunction "1_1") (pintype "passive"))
      (node (ref "C59") (pin "2") (pinfunction "2_2") (pintype "passive"))
      (node (ref "C6") (pin "1") (pinfunction "1_1") (pintype "passive"))
      (node (ref "C7") (pin "1") (pinfunction "1_1") (pintype "passive"))
      (node (ref "C8") (pin "1") (pinfunction "1_1") (pintype "passive"))
      (node (ref "C84") (pin "1") (pinfunction "1_1") (pintype "passive"))
      (node (ref "C85") (pin "1") (pinfunction "1_1") (pintype "passive"))
      (node (ref "C86") (pin "1") (pinfunction "1_1") (pintype "passive"))
      (node (ref "D52") (pin "1") (pinfunction "A_1") (pintype "passive"))
      (node (ref "E13") (pin "2") (pinfunction "2_2") (pintype "passive"))
      (node (ref "E14") (pin "2") (pinfunction "2_2") (pintype "passive"))
      (node (ref "P1") (pin "1") (pinfunction "1_1") (pintype "passive"))
      (node (ref "P1") (pin "3") (pinfunction "3_3") (pintype "passive"))
      (node (ref "P1") (pin "5") (pinfunction "5_5") (pintype "passive"))
      (node (ref "P1") (pin "6") (pinfunction "6_6") (pintype "passive"))
      (node (ref "R12") (pin "1") (pinfunction "1_1") (pintype "passive"))
      (node (ref "R14") (pin "1") (pinfunction "1_1") (pintype "passive"))
      (node (ref "R18") (pin "1") (pinfunction "1_1") (pintype "passive"))
      (node (ref "R23") (pin "1") (pinfunction "1_1") (pintype "passive"))
      (node (ref "R28") (pin "1") (pinfunction "1_1") (pintype "passive"))
      (node (ref "R33") (pin "1") (pinfunction "1_1") (pintype "passive"))
      (node (ref "R35") (pin "1") (pinfunction "1_1") (pintype "passive"))
      (node (ref "R38") (pin "1") (pinfunction "1_1") (pintype "passive"))
      (node (ref "R6") (pin "1") (pinfunction "1_1") (pintype "passive"))
      (node (ref "R89") (pin "1") (pinfunction "1_1") (pintype "passive"))
      (node (ref "U1") (pin "1") (pinfunction "GND_1") (pintype "power_in"))
      (node (ref "U1") (pin "2") (pinfunction "GND_2") (pintype "power_in"))
      (node (ref "U10") (pin "15") (pinfunction "GND2_15") (pintype "power_in"))
      (node (ref "U10") (pin "9") (pinfunction "GND2_9") (pintype "power_in"))
      (node (ref "U18") (pin "15") (pinfunction "GND2_15") (pintype "power_in"))
      (node (ref "U18") (pin "9") (pinfunction "GND2_9") (pintype "power_in"))
      (node (ref "U2") (pin "11") (pinfunction "GND_11") (pintype "power_in"))
      (node (ref "U3") (pin "11") (pinfunction "GND_11") (pintype "power_in"))
      (node (ref "U4") (pin "12") (pinfunction "CLKSEL_12") (pintype "input"))
      (node (ref "U4") (pin "14") (pinfunction "GPIO0_14") (pintype "bidirectional"))
      (node (ref "U4") (pin "15") (pinfunction "GPIO1_15") (pintype "bidirectional"))
      (node (ref "U4") (pin "16") (pinfunction "GPIO2_16") (pintype "bidirectional"))
      (node (ref "U4") (pin "20") (pinfunction "GPIO6_20") (pintype "bidirectional"))
      (node (ref "U4") (pin "21") (pinfunction "GPIO7_21") (pintype "bidirectional"))
      (node (ref "U4") (pin "29") (pinfunction "DGND_29") (pintype "power_in"))
      (node (ref "U4") (pin "30") (pinfunction "VREFN_30") (pintype "input"))
      (node (ref "U4") (pin "32") (pinfunction "AINCOM_32") (pintype "input"))
      (node (ref "U4") (pin "49") (pinfunction "EP_49") (pintype "passive"))
      (node (ref "U4") (pin "5") (pinfunction "AVSS_5") (pintype "power_in"))
      (node (ref "U7") (pin "11") (pinfunction "GND_11") (pintype "power_in"))
      (node (ref "U9") (pin "2") (pinfunction "GND1_2") (pintype "power_in"))
      (node (ref "U9") (pin "8") (pinfunction "GND1_8") (pintype "power_in"))
    )
    (net (code "64") (name "GND") (class "Default")
      (node (ref "C147") (pin "1") (pinfunction "1_1") (pintype "passive"))
      (node (ref "C161") (pin "1") (pinfunction "1_1") (pintype "passive"))
      (node (ref "C163") (pin "1") (pinfunction "1_1") (pintype "passive"))
      (node (ref "U10") (pin "2") (pinfunction "GND1_2") (pintype "power_in"))
      (node (ref "U10") (pin "8") (pinfunction "GND1_8") (pintype "power_in"))
      (node (ref "U18") (pin "2") (pinfunction "GND1_2") (pintype "power_in"))
      (node (ref "U18") (pin "8") (pinfunction "GND1_8") (pintype "power_in"))
      (node (ref "U9") (pin "15") (pinfunction "GND2_15") (pintype "power_in"))
      (node (ref "U9") (pin "9") (pinfunction "GND2_9") (pintype "power_in"))
    )
    (net (code "65") (name "Net-(C3-Pad1)") (class "Default")
      (node (ref "C3") (pin "1") (pinfunction "1_1") (pintype "passive"))
      (node (ref "R1") (pin "1") (pinfunction "1_1") (pintype "passive"))
      (node (ref "R2") (pin "2") (pinfunction "2_2") (pintype "passive"))
    )
    (net (code "66") (name "Net-(C4-Pad1)") (class "Default")
      (node (ref "C4") (pin "1") (pinfunction "1_1") (pintype "passive"))
      (node (ref "R3") (pin "1") (pinfunction "1_1") (pintype "passive"))
      (node (ref "R4") (pin "2") (pinfunction "2_2") (pintype "passive"))
    )
    (net (code "67") (name "Net-(C5-Pad1)") (class "Default")
      (node (ref "C5") (pin "1") (pinfunction "1_1") (pintype "passive"))
      (node (ref "R7") (pin "1") (pinfunction "1_1") (pintype "passive"))
      (node (ref "R8") (pin "2") (pinfunction "2_2") (pintype "passive"))
    )
    (net (code "68") (name "Net-(C12-Pad1)") (class "Default")
      (node (ref "C12") (pin "1") (pinfunction "1_1") (pintype "passive"))
      (node (ref "R25") (pin "1") (pinfunction "1_1") (pintype "passive"))
      (node (ref "R26") (pin "2") (pinfunction "2_2") (pintype "passive"))
    )
    (net (code "69") (name "Net-(C13-Pad1)") (class "Default")
      (node (ref "C13") (pin "1") (pinfunction "1_1") (pintype "passive"))
      (node (ref "R29") (pin "1") (pinfunction "1_1") (pintype "passive"))
      (node (ref "R30") (pin "2") (pinfunction "2_2") (pintype "passive"))
    )
    (net (code "70") (name "Net-(C21-Pad1)") (class "Default")
      (node (ref "C21") (pin "1") (pinfunction "1_1") (pintype "passive"))
      (node (ref "R44") (pin "1") (pinfunction "1_1") (pintype "passive"))
      (node (ref "R45") (pin "2") (pinfunction "2_2") (pintype "passive"))
    )
    (net (code "71") (name "Net-(C22-Pad1)") (class "Default")
      (node (ref "C22") (pin "1") (pinfunction "1_1") (pintype "passive"))
      (node (ref "R46") (pin "1") (pinfunction "1_1") (pintype "passive"))
      (node (ref "R47") (pin "2") (pinfunction "2_2") (pintype "passive"))
    )
    (net (code "72") (name "Net-(C29-Pad1)") (class "Default")
      (node (ref "C29") (pin "1") (pinfunction "1_1") (pintype "passive"))
      (node (ref "R60") (pin "1") (pinfunction "1_1") (pintype "passive"))
      (node (ref "R61") (pin "2") (pinfunction "2_2") (pintype "passive"))
    )
    (net (code "73") (name "Net-(C30-Pad1)") (class "Default")
      (node (ref "C30") (pin "1") (pinfunction "1_1") (pintype "passive"))
      (node (ref "R62") (pin "1") (pinfunction "1_1") (pintype "passive"))
      (node (ref "R63") (pin "2") (pinfunction "2_2") (pintype "passive"))
    )
    (net (code "74") (name "Net-(D1-K)") (class "Default")
      (node (ref "D1") (pin "2") (pinfunction "K_2") (pintype "passive"))
      (node (ref "D12") (pin "1") (pinfunction "A_1") (pintype "passive"))
    )
    (net (code "75") (name "Net-(D2-K)") (class "Default")
      (node (ref "D2") (pin "2") (pinfunction "K_2") (pintype "passive"))
      (node (ref "D3") (pin "1") (pinfunction "A_1") (pintype "passive"))
    )
    (net (code "76") (name "Net-(D5-K)") (class "Default")
      (node (ref "D5") (pin "2") (pinfunction "K_2") (pintype "passive"))
      (node (ref "D6") (pin "1") (pinfunction "A_1") (pintype "passive"))
    )
    (net (code "77") (name "Net-(D7-K)") (class "Default")
      (node (ref "D7") (pin "2") (pinfunction "K_2") (pintype "passive"))
      (node (ref "D9") (pin "1") (pinfunction "A_1") (pintype "passive"))
    )
    (net (code "78") (name "Net-(D10-K)") (class "Default")
      (node (ref "D10") (pin "2") (pinfunction "K_2") (pintype "passive"))
      (node (ref "D11") (pin "1") (pinfunction "A_1") (pintype "passive"))
    )
    (net (code "79") (name "Net-(D13-K)") (class "Default")
      (node (ref "D13") (pin "2") (pinfunction "K_2") (pintype "passive"))
      (node (ref "D14") (pin "1") (pinfunction "A_1") (pintype "passive"))
    )
    (net (code "80") (name "Net-(D16-K)") (class "Default")
      (node (ref "D16") (pin "2") (pinfunction "K_2") (pintype "passive"))
      (node (ref "D17") (pin "1") (pinfunction "A_1") (pintype "passive"))
    )
    (net (code "81") (name "Net-(D18-K)") (class "Default")
      (node (ref "D18") (pin "2") (pinfunction "K_2") (pintype "passive"))
      (node (ref "D19") (pin "1") (pinfunction "A_1") (pintype "passive"))
    )
    (net (code "82") (name "Net-(D20-K)") (class "Default")
      (node (ref "D20") (pin "2") (pinfunction "K_2") (pintype "passive"))
      (node (ref "D21") (pin "1") (pinfunction "A_1") (pintype "passive"))
    )
    (net (code "83") (name "Net-(P2-Pad2)") (class "Default")
      (node (ref "P2") (pin "2") (pinfunction "2_2") (pintype "passive"))
      (node (ref "R23") (pin "2") (pinfunction "2_2") (pintype "passive"))
      (node (ref "R24") (pin "1") (pinfunction "1_1") (pintype "passive"))
    )
    (net (code "84") (name "Net-(R5-Pad1)") (class "Default")
      (node (ref "R5") (pin "1") (pinfunction "1_1") (pintype "passive"))
      (node (ref "R6") (pin "2") (pinfunction "2_2") (pintype "passive"))
    )
    (net (code "85") (name "Net-(R11-Pad1)") (class "Default")
      (node (ref "R11") (pin "1") (pinfunction "1_1") (pintype "passive"))
      (node (ref "R12") (pin "2") (pinfunction "2_2") (pintype "passive"))
    )
    (net (code "86") (name "Net-(R13-Pad1)") (class "Default")
      (node (ref "R13") (pin "1") (pinfunction "1_1") (pintype "passive"))
      (node (ref "R14") (pin "2") (pinfunction "2_2") (pintype "passive"))
    )
    (net (code "87") (name "Net-(R17-Pad1)") (class "Default")
      (node (ref "R17") (pin "1") (pinfunction "1_1") (pintype "passive"))
      (node (ref "R18") (pin "2") (pinfunction "2_2") (pintype "passive"))
    )
    (net (code "88") (name "Net-(R27-Pad1)") (class "Default")
      (node (ref "R27") (pin "1") (pinfunction "1_1") (pintype "passive"))
      (node (ref "R28") (pin "2") (pinfunction "2_2") (pintype "passive"))
    )
    (net (code "89") (name "Net-(R32-Pad1)") (class "Default")
      (node (ref "R32") (pin "1") (pinfunction "1_1") (pintype "passive"))
      (node (ref "R33") (pin "2") (pinfunction "2_2") (pintype "passive"))
    )
    (net (code "90") (name "Net-(R34-Pad1)") (class "Default")
      (node (ref "R34") (pin "1") (pinfunction "1_1") (pintype "passive"))
      (node (ref "R35") (pin "2") (pinfunction "2_2") (pintype "passive"))
    )
    (net (code "91") (name "Net-(R36-Pad1)") (class "Default")
      (node (ref "R36") (pin "1") (pinfunction "1_1") (pintype "passive"))
      (node (ref "R38") (pin "2") (pinfunction "2_2") (pintype "passive"))
    )
    (net (code "92") (name "Net-(R80-Pad1)") (class "Default")
      (node (ref "R80") (pin "1") (pinfunction "1_1") (pintype "passive"))
      (node (ref "R89") (pin "2") (pinfunction "2_2") (pintype "passive"))
    )
    (net (code "93") (name "Net-(U2A-IN+)") (class "Default")
      (node (ref "C6") (pin "2") (pinfunction "2_2") (pintype "passive"))
      (node (ref "R2") (pin "1") (pinfunction "1_1") (pintype "passive"))
      (node (ref "U2") (pin "3") (pinfunction "IN+_3") (pintype "input"))
    )
    (net (code "94") (name "Net-(U2B-IN+)") (class "Default")
      (node (ref "C17") (pin "2") (pinfunction "2_2") (pintype "passive"))
      (node (ref "R30") (pin "1") (pinfunction "1_1") (pintype "passive"))
      (node (ref "U2") (pin "5") (pinfunction "IN+_5") (pintype "input"))
    )
    (net (code "95") (name "Net-(U2C-IN+)") (class "Default")
      (node (ref "C8") (pin "2") (pinfunction "2_2") (pintype "passive"))
      (node (ref "R8") (pin "1") (pinfunction "1_1") (pintype "passive"))
      (node (ref "U2") (pin "10") (pinfunction "IN+_10") (pintype "input"))
    )
    (net (code "96") (name "Net-(U3A-IN+)") (class "Default")
      (node (ref "C16") (pin "2") (pinfunction "2_2") (pintype "passive"))
      (node (ref "R26") (pin "1") (pinfunction "1_1") (pintype "passive"))
      (node (ref "U3") (pin "3") (pinfunction "IN+_3") (pintype "input"))
    )
    (net (code "97") (name "Net-(U3B-IN+)") (class "Default")
      (node (ref "C7") (pin "2") (pinfunction "2_2") (pintype "passive"))
      (node (ref "R4") (pin "1") (pinfunction "1_1") (pintype "passive"))
      (node (ref "U3") (pin "5") (pinfunction "IN+_5") (pintype "input"))
    )
    (net (code "98") (name "Net-(U3C-IN+)") (class "Default")
      (node (ref "C25") (pin "2") (pinfunction "2_2") (pintype "passive"))
      (node (ref "R45") (pin "1") (pinfunction "1_1") (pintype "passive"))
      (node (ref "U3") (pin "10") (pinfunction "IN+_10") (pintype "input"))
    )
    (net (code "99") (name "Net-(U4-CLKIO)") (class "Default")
      (node (ref "TP18") (pin "1") (pinfunction "1_1") (pintype "passive"))
      (node (ref "U4") (pin "13") (pinfunction "CLKIO_13") (pintype "bidirectional"))
    )
    (net (code "100") (name "Net-(U4-PLLCAP)") (class "Default")
      (node (ref "C43") (pin "1") (pinfunction "1_1") (pintype "passive"))
      (node (ref "U4") (pin "7") (pinfunction "PLLCAP_7") (pintype "power_in"))
    )
    (net (code "101") (name "Net-(U4-XTAL1)") (class "Default")
      (node (ref "C59") (pin "1") (pinfunction "1_1") (pintype "passive"))
      (node (ref "U4") (pin "8") (pinfunction "XTAL1_8") (pintype "passive"))
      (node (ref "X2") (pin "2") (pinfunction "OSC2_2") (pintype "passive"))
    )
    (net (code "102") (name "Net-(U4-XTAL2)") (class "Default")
      (node (ref "C48") (pin "1") (pinfunction "1_1") (pintype "passive"))
      (node (ref "U4") (pin "9") (pinfunction "XTAL2_9") (pintype "passive"))
      (node (ref "X2") (pin "1") (pinfunction "OSC1_1") (pintype "passive"))
    )
    (net (code "103") (name "Net-(U4-~{PWDN})") (class "Default")
      (node (ref "R20") (pin "2") (pinfunction "2_2") (pintype "passive"))
      (node (ref "U4") (pin "10") (pinfunction "~{PWDN}_10") (pintype "input"))
    )
    (net (code "104") (name "Net-(U4-~{RESET})") (class "Default")
      (node (ref "R73") (pin "2") (pinfunction "2_2") (pintype "passive"))
      (node (ref "U4") (pin "11") (pinfunction "~{RESET}_11") (pintype "input"))
    )
    (net (code "105") (name "Net-(U7A-IN+)") (class "Default")
      (node (ref "C26") (pin "2") (pinfunction "2_2") (pintype "passive"))
      (node (ref "R47") (pin "1") (pinfunction "1_1") (pintype "passive"))
      (node (ref "U7") (pin "3") (pinfunction "IN+_3") (pintype "input"))
    )
    (net (code "106") (name "Net-(U7B-IN+)") (class "Default")
      (node (ref "C33") (pin "2") (pinfunction "2_2") (pintype "passive"))
      (node (ref "R61") (pin "1") (pinfunction "1_1") (pintype "passive"))
      (node (ref "U7") (pin "5") (pinfunction "IN+_5") (pintype "input"))
    )
    (net (code "107") (name "Net-(U7C-IN+)") (class "Default")
      (node (ref "C34") (pin "2") (pinfunction "2_2") (pintype "passive"))
      (node (ref "R63") (pin "1") (pinfunction "1_1") (pintype "passive"))
      (node (ref "U7") (pin "10") (pinfunction "IN+_10") (pintype "input"))
    )
    (net (code "108") (name "VCC_5V_ISO") (class "Default")
      (node (ref "FB1") (pin "1") (pintype "passive"))
      (node (ref "FB2") (pin "1") (pintype "passive"))
      (node (ref "FB4") (pin "1") (pintype "passive"))
    )
    (net (code "109") (name "unconnected-(U1-DNC-Pad3)") (class "Default")
      (node (ref "U1") (pin "3") (pinfunction "DNC_3") (pintype "passive"))
    )
    (net (code "110") (name "unconnected-(U1-DNC-Pad5)") (class "Default")
      (node (ref "U1") (pin "5") (pinfunction "DNC_5") (pintype "passive"))
    )
    (net (code "111") (name "unconnected-(U4-ADCINN-Pad41)") (class "Default")
      (node (ref "U4") (pin "41") (pinfunction "ADCINN_41") (pintype "input"))
    )
    (net (code "112") (name "unconnected-(U4-ADCINP-Pad42)") (class "Default")
      (node (ref "U4") (pin "42") (pinfunction "ADCINP_42") (pintype "input"))
    )
    (net (code "113") (name "unconnected-(U4-GPIO3-Pad17)") (class "Default")
      (node (ref "U4") (pin "17") (pinfunction "GPIO3_17") (pintype "bidirectional"))
    )
    (net (code "114") (name "unconnected-(U4-GPIO4-Pad18)") (class "Default")
      (node (ref "U4") (pin "18") (pinfunction "GPIO4_18") (pintype "bidirectional"))
    )
    (net (code "115") (name "unconnected-(U4-GPIO5-Pad19)") (class "Default")
      (node (ref "U4") (pin "19") (pinfunction "GPIO5_19") (pintype "bidirectional"))
    )
    (net (code "116") (name "unconnected-(U4-MUXOUTN-Pad43)") (class "Default")
      (node (ref "U4") (pin "43") (pinfunction "MUXOUTN_43") (pintype "output+no_connect"))
    )
    (net (code "117") (name "unconnected-(U4-MUXOUTP-Pad44)") (class "Default")
      (node (ref "U4") (pin "44") (pinfunction "MUXOUTP_44") (pintype "output+no_connect"))
    )
    (net (code "118") (name "unconnected-(U10-INC-Pad5)") (class "Default")
      (node (ref "U10") (pin "5") (pinfunction "INC_5") (pintype "input"))
    )
    (net (code "119") (name "unconnected-(U10-IND-Pad11)") (class "Default")
      (node (ref "U10") (pin "11") (pinfunction "IND_11") (pintype "input"))
    )
    (net (code "120") (name "unconnected-(U10-OUTC-Pad12)") (class "Default")
      (node (ref "U10") (pin "12") (pinfunction "OUTC_12") (pintype "output"))
    )
    (net (code "121") (name "unconnected-(U10-OUTD-Pad6)") (class "Default")
      (node (ref "U10") (pin "6") (pinfunction "OUTD_6") (pintype "output"))
    )
  )
)
